# CommonBoard_FK_H743.net
KiCad netlist of a schematic drawn in Altium Designer
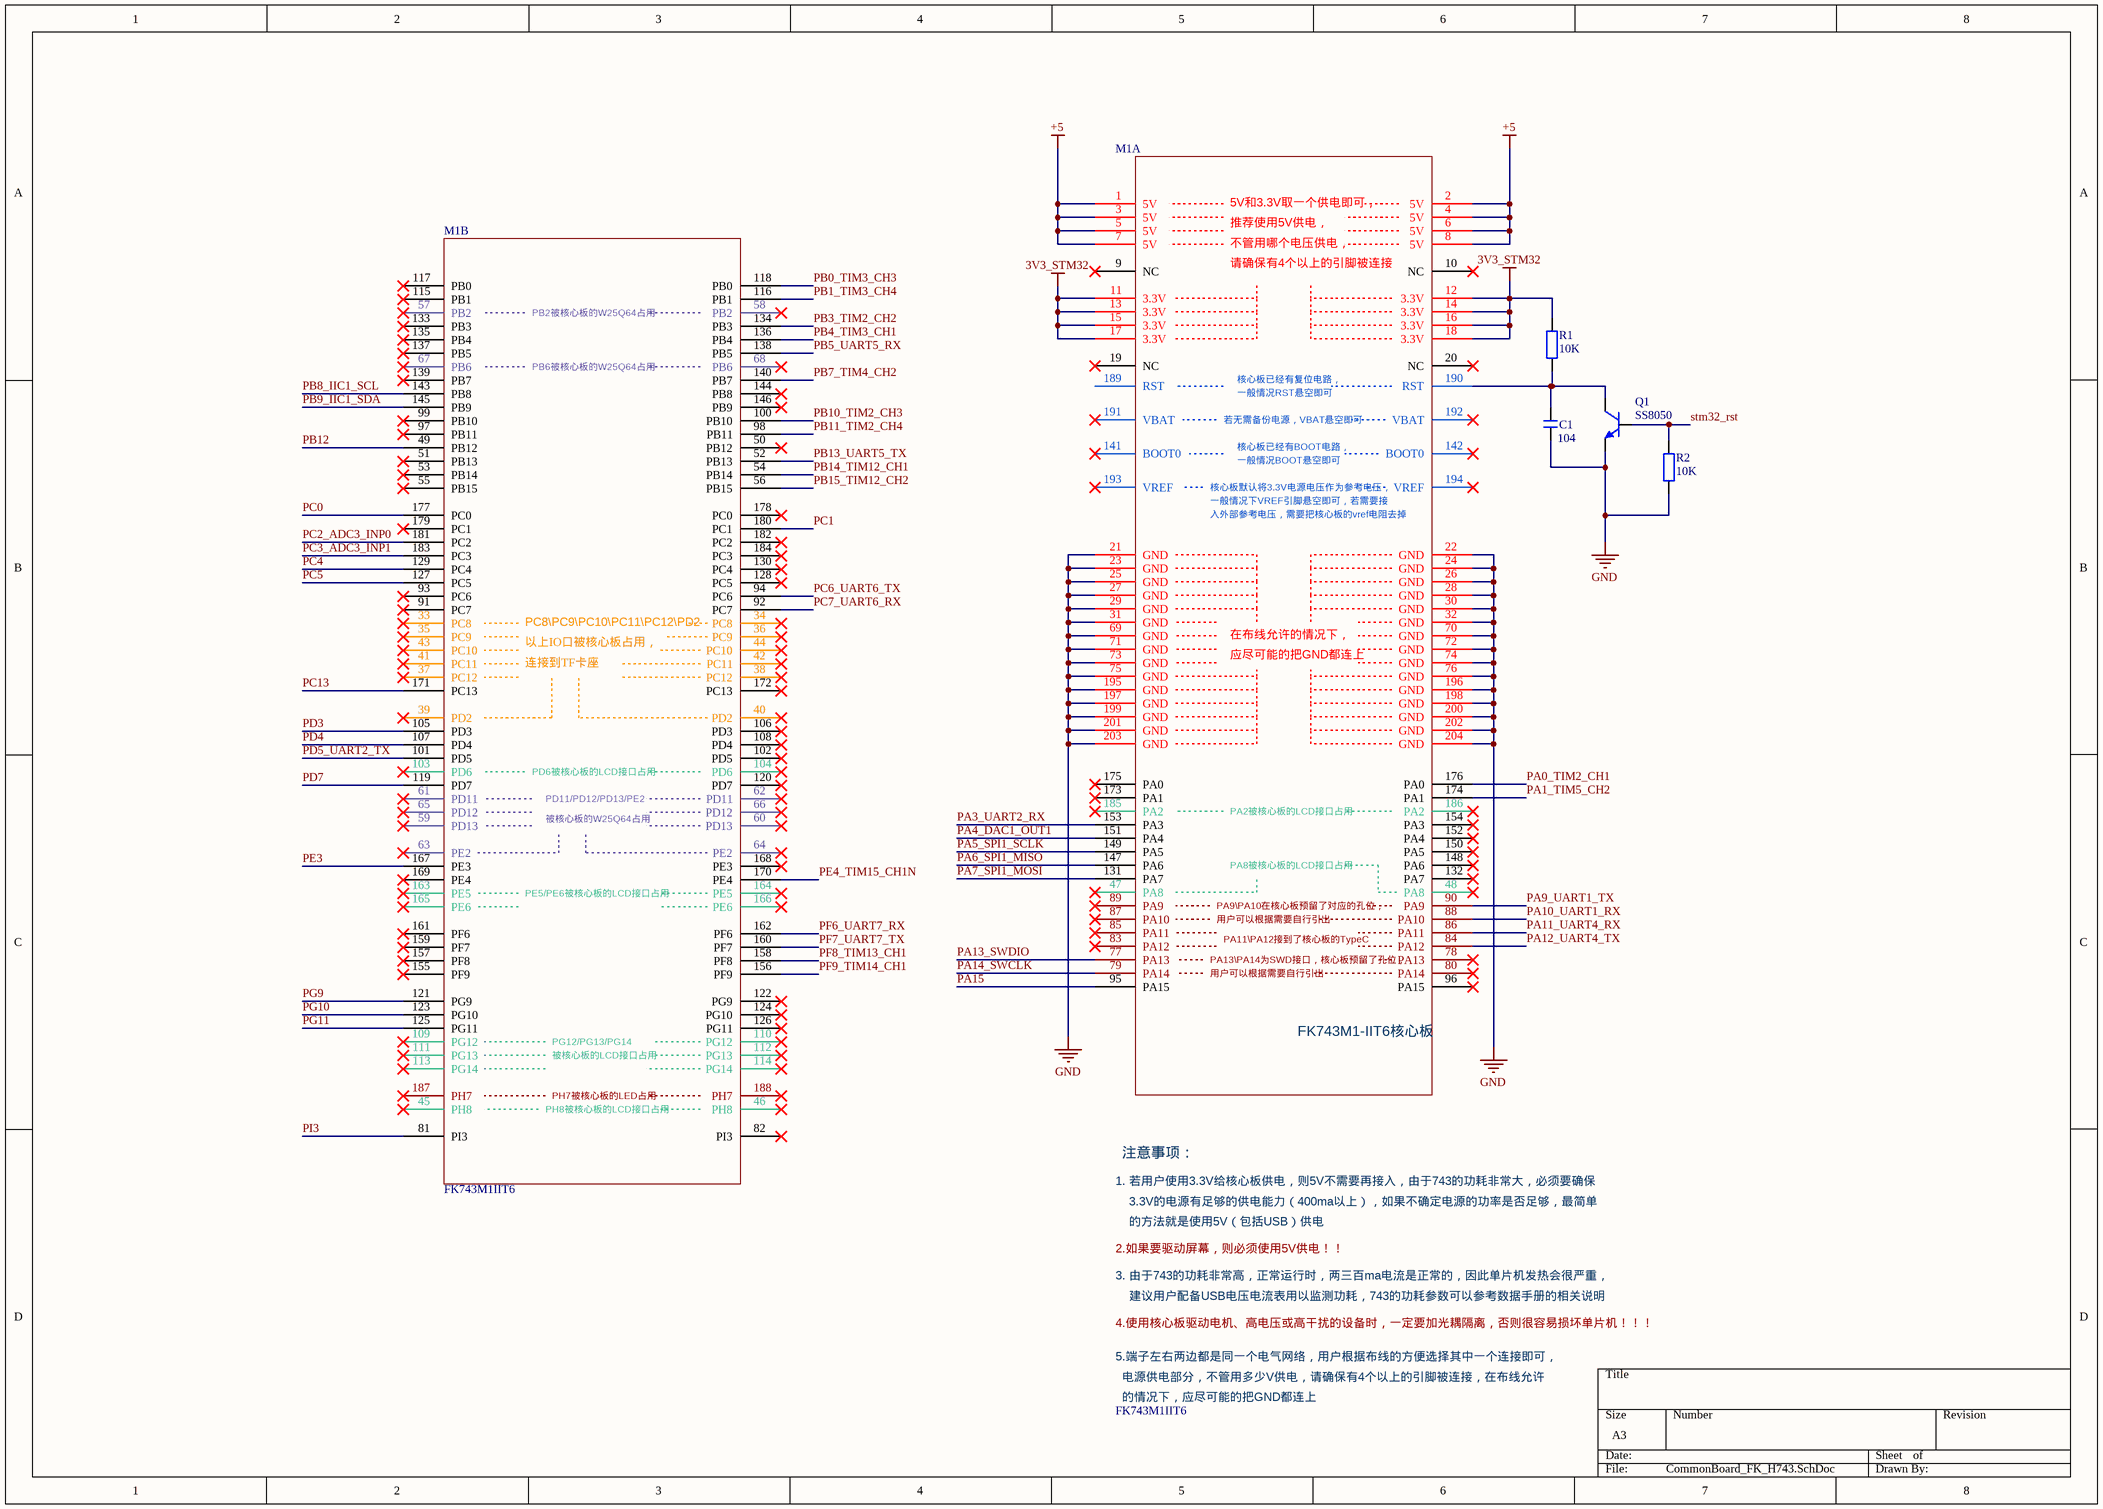
[diagram p0: CommonBoard_FK_H743.SchDoc]

(export (version "E")
  (design (tool "Eeschema 10.0.6"))
  (components
    (comp (ref "C1")
      (value "104")
      (footprint "C 0603_L")
      (description "无极性贴片电容")
      (fields (field (name "版权归属") "源创客"))
      (libsource (lib "3.1   - 电阻-电容-电感") (part "C"))
    )
    (comp (ref "M1")
      (value "FK743M1IIT6")
      (footprint "FK743M1-IIT6")
      (libsource (lib "MySchLib") (part "FK743M1-IIT6"))
    )
    (comp (ref "Q1")
      (value "SS8050")
      (footprint "SOT23-3N")
      (description "高频放大-NPN型")
      (fields (field (name "版权归属") "源创客"))
      (libsource (lib "6.2   - 三极管") (part "8050-SMD"))
    )
    (comp (ref "R1")
      (value "10K")
      (footprint "R 0603_L")
      (description "贴片电阻")
      (fields (field (name "版权归属") "源创客"))
      (libsource (lib "3.1   - 电阻-电容-电感") (part "R"))
    )
    (comp (ref "R2")
      (value "10K")
      (footprint "R 0603_L")
      (description "贴片电阻")
      (fields (field (name "版权归属") "源创客"))
      (libsource (lib "3.1   - 电阻-电容-电感") (part "R"))
    )
  )
  (nets
    (net (code "1") (name "+5") (class "Default")
      (node (ref "M1") (pin "1") (pinfunction "5V_1") (pintype "passive"))
      (node (ref "M1") (pin "2") (pinfunction "5V_2") (pintype "passive"))
      (node (ref "M1") (pin "3") (pinfunction "5V_3") (pintype "passive"))
      (node (ref "M1") (pin "4") (pinfunction "5V_4") (pintype "passive"))
      (node (ref "M1") (pin "5") (pinfunction "5V_5") (pintype "passive"))
      (node (ref "M1") (pin "6") (pinfunction "5V_6") (pintype "passive"))
      (node (ref "M1") (pin "7") (pinfunction "5V_7") (pintype "passive"))
      (node (ref "M1") (pin "8") (pinfunction "5V_8") (pintype "passive"))
    )
    (net (code "2") (name "/PA0_TIM2_CH1") (class "Default")
      (node (ref "M1") (pin "176") (pinfunction "PA0_176") (pintype "passive"))
    )
    (net (code "3") (name "/PA1_TIM5_CH2") (class "Default")
      (node (ref "M1") (pin "174") (pinfunction "PA1_174") (pintype "passive"))
    )
    (net (code "4") (name "/PA3_UART2_RX") (class "Default")
      (node (ref "M1") (pin "153") (pinfunction "PA3_153") (pintype "passive"))
    )
    (net (code "5") (name "/PA4_DAC1_OUT1") (class "Default")
      (node (ref "M1") (pin "151") (pinfunction "PA4_151") (pintype "passive"))
    )
    (net (code "6") (name "/PA5_SPI1_SCLK") (class "Default")
      (node (ref "M1") (pin "149") (pinfunction "PA5_149") (pintype "passive"))
    )
    (net (code "7") (name "/PA6_SPI1_MISO") (class "Default")
      (node (ref "M1") (pin "147") (pinfunction "PA6_147") (pintype "passive"))
    )
    (net (code "8") (name "/PA7_SPI1_MOSI") (class "Default")
      (node (ref "M1") (pin "131") (pinfunction "PA7_131") (pintype "passive"))
    )
    (net (code "9") (name "/PA9_UART1_TX") (class "Default")
      (node (ref "M1") (pin "90") (pinfunction "PA9_90") (pintype "passive"))
    )
    (net (code "10") (name "/PA10_UART1_RX") (class "Default")
      (node (ref "M1") (pin "88") (pinfunction "PA10_88") (pintype "passive"))
    )
    (net (code "11") (name "/PA11_UART4_RX") (class "Default")
      (node (ref "M1") (pin "86") (pinfunction "PA11_86") (pintype "passive"))
    )
    (net (code "12") (name "/PA12_UART4_TX") (class "Default")
      (node (ref "M1") (pin "84") (pinfunction "PA12_84") (pintype "passive"))
    )
    (net (code "13") (name "/PA13_SWDIO") (class "Default")
      (node (ref "M1") (pin "77") (pinfunction "PA13_77") (pintype "passive"))
    )
    (net (code "14") (name "/PA14_SWCLK") (class "Default")
      (node (ref "M1") (pin "79") (pinfunction "PA14_79") (pintype "passive"))
    )
    (net (code "15") (name "/PA15") (class "Default")
      (node (ref "M1") (pin "95") (pinfunction "PA15_95") (pintype "passive"))
    )
    (net (code "16") (name "/PB0_TIM3_CH3") (class "Default")
      (node (ref "M1") (pin "118") (pinfunction "PB0_118") (pintype "passive"))
    )
    (net (code "17") (name "/PB1_TIM3_CH4") (class "Default")
      (node (ref "M1") (pin "116") (pinfunction "PB1_116") (pintype "passive"))
    )
    (net (code "18") (name "/PB3_TIM2_CH2") (class "Default")
      (node (ref "M1") (pin "134") (pinfunction "PB3_134") (pintype "passive"))
    )
    (net (code "19") (name "/PB4_TIM3_CH1") (class "Default")
      (node (ref "M1") (pin "136") (pinfunction "PB4_136") (pintype "passive"))
    )
    (net (code "20") (name "/PB5_UART5_RX") (class "Default")
      (node (ref "M1") (pin "138") (pinfunction "PB5_138") (pintype "passive"))
    )
    (net (code "21") (name "/PB7_TIM4_CH2") (class "Default")
      (node (ref "M1") (pin "140") (pinfunction "PB7_140") (pintype "passive"))
    )
    (net (code "22") (name "/PB8_IIC1_SCL") (class "Default")
      (node (ref "M1") (pin "143") (pinfunction "PB8_143") (pintype "passive"))
    )
    (net (code "23") (name "/PB9_IIC1_SDA") (class "Default")
      (node (ref "M1") (pin "145") (pinfunction "PB9_145") (pintype "passive"))
    )
    (net (code "24") (name "/PB10_TIM2_CH3") (class "Default")
      (node (ref "M1") (pin "100") (pinfunction "PB10_100") (pintype "passive"))
    )
    (net (code "25") (name "/PB11_TIM2_CH4") (class "Default")
      (node (ref "M1") (pin "98") (pinfunction "PB11_98") (pintype "passive"))
    )
    (net (code "26") (name "/PB12") (class "Default")
      (node (ref "M1") (pin "49") (pinfunction "PB12_49") (pintype "passive"))
    )
    (net (code "27") (name "/PB13_UART5_TX") (class "Default")
      (node (ref "M1") (pin "52") (pinfunction "PB13_52") (pintype "passive"))
    )
    (net (code "28") (name "/PB14_TIM12_CH1") (class "Default")
      (node (ref "M1") (pin "54") (pinfunction "PB14_54") (pintype "passive"))
    )
    (net (code "29") (name "/PB15_TIM12_CH2") (class "Default")
      (node (ref "M1") (pin "56") (pinfunction "PB15_56") (pintype "passive"))
    )
    (net (code "30") (name "/PC0") (class "Default")
      (node (ref "M1") (pin "177") (pinfunction "PC0_177") (pintype "passive"))
    )
    (net (code "31") (name "/PC1") (class "Default")
      (node (ref "M1") (pin "180") (pinfunction "PC1_180") (pintype "passive"))
    )
    (net (code "32") (name "/PC2_ADC3_INP0") (class "Default")
      (node (ref "M1") (pin "181") (pinfunction "PC2_181") (pintype "passive"))
    )
    (net (code "33") (name "/PC3_ADC3_INP1") (class "Default")
      (node (ref "M1") (pin "183") (pinfunction "PC3_183") (pintype "passive"))
    )
    (net (code "34") (name "/PC4") (class "Default")
      (node (ref "M1") (pin "129") (pinfunction "PC4_129") (pintype "passive"))
    )
    (net (code "35") (name "/PC5") (class "Default")
      (node (ref "M1") (pin "127") (pinfunction "PC5_127") (pintype "passive"))
    )
    (net (code "36") (name "/PC6_UART6_TX") (class "Default")
      (node (ref "M1") (pin "94") (pinfunction "PC6_94") (pintype "passive"))
    )
    (net (code "37") (name "/PC7_UART6_RX") (class "Default")
      (node (ref "M1") (pin "92") (pinfunction "PC7_92") (pintype "passive"))
    )
    (net (code "38") (name "/PC13") (class "Default")
      (node (ref "M1") (pin "171") (pinfunction "PC13_171") (pintype "passive"))
    )
    (net (code "39") (name "/PD3") (class "Default")
      (node (ref "M1") (pin "105") (pinfunction "PD3_105") (pintype "passive"))
    )
    (net (code "40") (name "/PD4") (class "Default")
      (node (ref "M1") (pin "107") (pinfunction "PD4_107") (pintype "passive"))
    )
    (net (code "41") (name "/PD5_UART2_TX") (class "Default")
      (node (ref "M1") (pin "101") (pinfunction "PD5_101") (pintype "passive"))
    )
    (net (code "42") (name "/PD7") (class "Default")
      (node (ref "M1") (pin "119") (pinfunction "PD7_119") (pintype "passive"))
    )
    (net (code "43") (name "/PE3") (class "Default")
      (node (ref "M1") (pin "167") (pinfunction "PE3_167") (pintype "passive"))
    )
    (net (code "44") (name "/PE4_TIM15_CH1N") (class "Default")
      (node (ref "M1") (pin "170") (pinfunction "PE4_170") (pintype "passive"))
    )
    (net (code "45") (name "/PF6_UART7_RX") (class "Default")
      (node (ref "M1") (pin "162") (pinfunction "PF6_162") (pintype "passive"))
    )
    (net (code "46") (name "/PF7_UART7_TX") (class "Default")
      (node (ref "M1") (pin "160") (pinfunction "PF7_160") (pintype "passive"))
    )
    (net (code "47") (name "/PF8_TIM13_CH1") (class "Default")
      (node (ref "M1") (pin "158") (pinfunction "PF8_158") (pintype "passive"))
    )
    (net (code "48") (name "/PF9_TIM14_CH1") (class "Default")
      (node (ref "M1") (pin "156") (pinfunction "PF9_156") (pintype "passive"))
    )
    (net (code "49") (name "/PG9") (class "Default")
      (node (ref "M1") (pin "121") (pinfunction "PG9_121") (pintype "passive"))
    )
    (net (code "50") (name "/PG10") (class "Default")
      (node (ref "M1") (pin "123") (pinfunction "PG10_123") (pintype "passive"))
    )
    (net (code "51") (name "/PG11") (class "Default")
      (node (ref "M1") (pin "125") (pinfunction "PG11_125") (pintype "passive"))
    )
    (net (code "52") (name "/PI3") (class "Default")
      (node (ref "M1") (pin "81") (pinfunction "PI3_81") (pintype "passive"))
    )
    (net (code "53") (name "/stm32_rst") (class "Default")
      (node (ref "Q1") (pin "1") (pinfunction "B_1") (pintype "passive"))
      (node (ref "R2") (pin "2") (pinfunction "2_2") (pintype "passive"))
    )
    (net (code "54") (name "3V3_STM32") (class "Default")
      (node (ref "M1") (pin "11") (pinfunction "3.3V_11") (pintype "passive"))
      (node (ref "M1") (pin "12") (pinfunction "3.3V_12") (pintype "passive"))
      (node (ref "M1") (pin "13") (pinfunction "3.3V_13") (pintype "passive"))
      (node (ref "M1") (pin "14") (pinfunction "3.3V_14") (pintype "passive"))
      (node (ref "M1") (pin "15") (pinfunction "3.3V_15") (pintype "passive"))
      (node (ref "M1") (pin "16") (pinfunction "3.3V_16") (pintype "passive"))
      (node (ref "M1") (pin "17") (pinfunction "3.3V_17") (pintype "passive"))
      (node (ref "M1") (pin "18") (pinfunction "3.3V_18") (pintype "passive"))
      (node (ref "R1") (pin "2") (pinfunction "2_2") (pintype "passive"))
    )
    (net (code "55") (name "GND") (class "Default")
      (node (ref "C1") (pin "1") (pinfunction "1_1") (pintype "passive"))
      (node (ref "M1") (pin "195") (pinfunction "GND_195") (pintype "passive"))
      (node (ref "M1") (pin "196") (pinfunction "GND_196") (pintype "passive"))
      (node (ref "M1") (pin "197") (pinfunction "GND_197") (pintype "passive"))
      (node (ref "M1") (pin "198") (pinfunction "GND_198") (pintype "passive"))
      (node (ref "M1") (pin "199") (pinfunction "GND_199") (pintype "passive"))
      (node (ref "M1") (pin "200") (pinfunction "GND_200") (pintype "passive"))
      (node (ref "M1") (pin "201") (pinfunction "GND_201") (pintype "passive"))
      (node (ref "M1") (pin "202") (pinfunction "GND_202") (pintype "passive"))
      (node (ref "M1") (pin "203") (pinfunction "GND_203") (pintype "passive"))
      (node (ref "M1") (pin "204") (pinfunction "GND_204") (pintype "passive"))
      (node (ref "M1") (pin "21") (pinfunction "GND_21") (pintype "passive"))
      (node (ref "M1") (pin "22") (pinfunction "GND_22") (pintype "passive"))
      (node (ref "M1") (pin "23") (pinfunction "GND_23") (pintype "passive"))
      (node (ref "M1") (pin "24") (pinfunction "GND_24") (pintype "passive"))
      (node (ref "M1") (pin "25") (pinfunction "GND_25") (pintype "passive"))
      (node (ref "M1") (pin "26") (pinfunction "GND_26") (pintype "passive"))
      (node (ref "M1") (pin "27") (pinfunction "GND_27") (pintype "passive"))
      (node (ref "M1") (pin "28") (pinfunction "GND_28") (pintype "passive"))
      (node (ref "M1") (pin "29") (pinfunction "GND_29") (pintype "passive"))
      (node (ref "M1") (pin "30") (pinfunction "GND_30") (pintype "passive"))
      (node (ref "M1") (pin "31") (pinfunction "GND_31") (pintype "passive"))
      (node (ref "M1") (pin "32") (pinfunction "GND_32") (pintype "passive"))
      (node (ref "M1") (pin "69") (pinfunction "GND_69") (pintype "passive"))
      (node (ref "M1") (pin "70") (pinfunction "GND_70") (pintype "passive"))
      (node (ref "M1") (pin "71") (pinfunction "GND_71") (pintype "passive"))
      (node (ref "M1") (pin "72") (pinfunction "GND_72") (pintype "passive"))
      (node (ref "M1") (pin "73") (pinfunction "GND_73") (pintype "passive"))
      (node (ref "M1") (pin "74") (pinfunction "GND_74") (pintype "passive"))
      (node (ref "M1") (pin "75") (pinfunction "GND_75") (pintype "passive"))
      (node (ref "M1") (pin "76") (pinfunction "GND_76") (pintype "passive"))
      (node (ref "Q1") (pin "2") (pinfunction "E_2") (pintype "passive"))
      (node (ref "R2") (pin "1") (pinfunction "1_1") (pintype "passive"))
    )
    (net (code "56") (name "Net-(Q1-C)") (class "Default")
      (node (ref "C1") (pin "2") (pinfunction "2_2") (pintype "passive"))
      (node (ref "M1") (pin "190") (pinfunction "RST_190") (pintype "passive"))
      (node (ref "Q1") (pin "3") (pinfunction "C_3") (pintype "passive"))
      (node (ref "R1") (pin "1") (pinfunction "1_1") (pintype "passive"))
    )
    (net (code "57") (name "unconnected-(M1A-BOOT0-Pad141)") (class "Default")
      (node (ref "M1") (pin "141") (pinfunction "BOOT0_141") (pintype "passive+no_connect"))
    )
    (net (code "58") (name "unconnected-(M1A-BOOT0-Pad142)") (class "Default")
      (node (ref "M1") (pin "142") (pinfunction "BOOT0_142") (pintype "passive+no_connect"))
    )
    (net (code "59") (name "unconnected-(M1A-NC-Pad9)") (class "Default")
      (node (ref "M1") (pin "9") (pinfunction "NC_9") (pintype "passive+no_connect"))
    )
    (net (code "60") (name "unconnected-(M1A-NC-Pad10)") (class "Default")
      (node (ref "M1") (pin "10") (pinfunction "NC_10") (pintype "passive+no_connect"))
    )
    (net (code "61") (name "unconnected-(M1A-NC-Pad19)") (class "Default")
      (node (ref "M1") (pin "19") (pinfunction "NC_19") (pintype "passive+no_connect"))
    )
    (net (code "62") (name "unconnected-(M1A-NC-Pad20)") (class "Default")
      (node (ref "M1") (pin "20") (pinfunction "NC_20") (pintype "passive+no_connect"))
    )
    (net (code "63") (name "unconnected-(M1A-PA0-Pad175)") (class "Default")
      (node (ref "M1") (pin "175") (pinfunction "PA0_175") (pintype "passive+no_connect"))
    )
    (net (code "64") (name "unconnected-(M1A-PA1-Pad173)") (class "Default")
      (node (ref "M1") (pin "173") (pinfunction "PA1_173") (pintype "passive+no_connect"))
    )
    (net (code "65") (name "unconnected-(M1A-PA2-Pad185)") (class "Default")
      (node (ref "M1") (pin "185") (pinfunction "PA2_185") (pintype "passive+no_connect"))
    )
    (net (code "66") (name "unconnected-(M1A-PA2-Pad186)") (class "Default")
      (node (ref "M1") (pin "186") (pinfunction "PA2_186") (pintype "passive+no_connect"))
    )
    (net (code "67") (name "unconnected-(M1A-PA3-Pad154)") (class "Default")
      (node (ref "M1") (pin "154") (pinfunction "PA3_154") (pintype "passive+no_connect"))
    )
    (net (code "68") (name "unconnected-(M1A-PA4-Pad152)") (class "Default")
      (node (ref "M1") (pin "152") (pinfunction "PA4_152") (pintype "passive+no_connect"))
    )
    (net (code "69") (name "unconnected-(M1A-PA5-Pad150)") (class "Default")
      (node (ref "M1") (pin "150") (pinfunction "PA5_150") (pintype "passive+no_connect"))
    )
    (net (code "70") (name "unconnected-(M1A-PA6-Pad148)") (class "Default")
      (node (ref "M1") (pin "148") (pinfunction "PA6_148") (pintype "passive+no_connect"))
    )
    (net (code "71") (name "unconnected-(M1A-PA7-Pad132)") (class "Default")
      (node (ref "M1") (pin "132") (pinfunction "PA7_132") (pintype "passive+no_connect"))
    )
    (net (code "72") (name "unconnected-(M1A-PA8-Pad47)") (class "Default")
      (node (ref "M1") (pin "47") (pinfunction "PA8_47") (pintype "passive+no_connect"))
    )
    (net (code "73") (name "unconnected-(M1A-PA8-Pad48)") (class "Default")
      (node (ref "M1") (pin "48") (pinfunction "PA8_48") (pintype "passive+no_connect"))
    )
    (net (code "74") (name "unconnected-(M1A-PA9-Pad89)") (class "Default")
      (node (ref "M1") (pin "89") (pinfunction "PA9_89") (pintype "passive+no_connect"))
    )
    (net (code "75") (name "unconnected-(M1A-PA10-Pad87)") (class "Default")
      (node (ref "M1") (pin "87") (pinfunction "PA10_87") (pintype "passive+no_connect"))
    )
    (net (code "76") (name "unconnected-(M1A-PA11-Pad85)") (class "Default")
      (node (ref "M1") (pin "85") (pinfunction "PA11_85") (pintype "passive+no_connect"))
    )
    (net (code "77") (name "unconnected-(M1A-PA12-Pad83)") (class "Default")
      (node (ref "M1") (pin "83") (pinfunction "PA12_83") (pintype "passive+no_connect"))
    )
    (net (code "78") (name "unconnected-(M1A-PA13-Pad78)") (class "Default")
      (node (ref "M1") (pin "78") (pinfunction "PA13_78") (pintype "passive+no_connect"))
    )
    (net (code "79") (name "unconnected-(M1A-PA14-Pad80)") (class "Default")
      (node (ref "M1") (pin "80") (pinfunction "PA14_80") (pintype "passive+no_connect"))
    )
    (net (code "80") (name "unconnected-(M1A-PA15-Pad96)") (class "Default")
      (node (ref "M1") (pin "96") (pinfunction "PA15_96") (pintype "passive+no_connect"))
    )
    (net (code "81") (name "unconnected-(M1A-RST-Pad189)") (class "Default")
      (node (ref "M1") (pin "189") (pinfunction "RST_189") (pintype "passive"))
    )
    (net (code "82") (name "unconnected-(M1A-VBAT-Pad191)") (class "Default")
      (node (ref "M1") (pin "191") (pinfunction "VBAT_191") (pintype "passive+no_connect"))
    )
    (net (code "83") (name "unconnected-(M1A-VBAT-Pad192)") (class "Default")
      (node (ref "M1") (pin "192") (pinfunction "VBAT_192") (pintype "passive+no_connect"))
    )
    (net (code "84") (name "unconnected-(M1A-VREF-Pad193)") (class "Default")
      (node (ref "M1") (pin "193") (pinfunction "VREF_193") (pintype "passive+no_connect"))
    )
    (net (code "85") (name "unconnected-(M1A-VREF-Pad194)") (class "Default")
      (node (ref "M1") (pin "194") (pinfunction "VREF_194") (pintype "passive+no_connect"))
    )
    (net (code "86") (name "unconnected-(M1B-PB0-Pad117)") (class "Default")
      (node (ref "M1") (pin "117") (pinfunction "PB0_117") (pintype "passive+no_connect"))
    )
    (net (code "87") (name "unconnected-(M1B-PB1-Pad115)") (class "Default")
      (node (ref "M1") (pin "115") (pinfunction "PB1_115") (pintype "passive+no_connect"))
    )
    (net (code "88") (name "unconnected-(M1B-PB2-Pad57)") (class "Default")
      (node (ref "M1") (pin "57") (pinfunction "PB2_57") (pintype "passive+no_connect"))
    )
    (net (code "89") (name "unconnected-(M1B-PB2-Pad58)") (class "Default")
      (node (ref "M1") (pin "58") (pinfunction "PB2_58") (pintype "passive+no_connect"))
    )
    (net (code "90") (name "unconnected-(M1B-PB3-Pad133)") (class "Default")
      (node (ref "M1") (pin "133") (pinfunction "PB3_133") (pintype "passive+no_connect"))
    )
    (net (code "91") (name "unconnected-(M1B-PB4-Pad135)") (class "Default")
      (node (ref "M1") (pin "135") (pinfunction "PB4_135") (pintype "passive+no_connect"))
    )
    (net (code "92") (name "unconnected-(M1B-PB5-Pad137)") (class "Default")
      (node (ref "M1") (pin "137") (pinfunction "PB5_137") (pintype "passive+no_connect"))
    )
    (net (code "93") (name "unconnected-(M1B-PB6-Pad67)") (class "Default")
      (node (ref "M1") (pin "67") (pinfunction "PB6_67") (pintype "passive+no_connect"))
    )
    (net (code "94") (name "unconnected-(M1B-PB6-Pad68)") (class "Default")
      (node (ref "M1") (pin "68") (pinfunction "PB6_68") (pintype "passive+no_connect"))
    )
    (net (code "95") (name "unconnected-(M1B-PB7-Pad139)") (class "Default")
      (node (ref "M1") (pin "139") (pinfunction "PB7_139") (pintype "passive+no_connect"))
    )
    (net (code "96") (name "unconnected-(M1B-PB8-Pad144)") (class "Default")
      (node (ref "M1") (pin "144") (pinfunction "PB8_144") (pintype "passive+no_connect"))
    )
    (net (code "97") (name "unconnected-(M1B-PB9-Pad146)") (class "Default")
      (node (ref "M1") (pin "146") (pinfunction "PB9_146") (pintype "passive+no_connect"))
    )
    (net (code "98") (name "unconnected-(M1B-PB10-Pad99)") (class "Default")
      (node (ref "M1") (pin "99") (pinfunction "PB10_99") (pintype "passive+no_connect"))
    )
    (net (code "99") (name "unconnected-(M1B-PB11-Pad97)") (class "Default")
      (node (ref "M1") (pin "97") (pinfunction "PB11_97") (pintype "passive+no_connect"))
    )
    (net (code "100") (name "unconnected-(M1B-PB12-Pad50)") (class "Default")
      (node (ref "M1") (pin "50") (pinfunction "PB12_50") (pintype "passive+no_connect"))
    )
    (net (code "101") (name "unconnected-(M1B-PB13-Pad51)") (class "Default")
      (node (ref "M1") (pin "51") (pinfunction "PB13_51") (pintype "passive+no_connect"))
    )
    (net (code "102") (name "unconnected-(M1B-PB14-Pad53)") (class "Default")
      (node (ref "M1") (pin "53") (pinfunction "PB14_53") (pintype "passive+no_connect"))
    )
    (net (code "103") (name "unconnected-(M1B-PB15-Pad55)") (class "Default")
      (node (ref "M1") (pin "55") (pinfunction "PB15_55") (pintype "passive+no_connect"))
    )
    (net (code "104") (name "unconnected-(M1B-PC0-Pad178)") (class "Default")
      (node (ref "M1") (pin "178") (pinfunction "PC0_178") (pintype "passive+no_connect"))
    )
    (net (code "105") (name "unconnected-(M1B-PC1-Pad179)") (class "Default")
      (node (ref "M1") (pin "179") (pinfunction "PC1_179") (pintype "passive+no_connect"))
    )
    (net (code "106") (name "unconnected-(M1B-PC2-Pad182)") (class "Default")
      (node (ref "M1") (pin "182") (pinfunction "PC2_182") (pintype "passive+no_connect"))
    )
    (net (code "107") (name "unconnected-(M1B-PC3-Pad184)") (class "Default")
      (node (ref "M1") (pin "184") (pinfunction "PC3_184") (pintype "passive+no_connect"))
    )
    (net (code "108") (name "unconnected-(M1B-PC4-Pad130)") (class "Default")
      (node (ref "M1") (pin "130") (pinfunction "PC4_130") (pintype "passive+no_connect"))
    )
    (net (code "109") (name "unconnected-(M1B-PC5-Pad128)") (class "Default")
      (node (ref "M1") (pin "128") (pinfunction "PC5_128") (pintype "passive+no_connect"))
    )
    (net (code "110") (name "unconnected-(M1B-PC6-Pad93)") (class "Default")
      (node (ref "M1") (pin "93") (pinfunction "PC6_93") (pintype "passive+no_connect"))
    )
    (net (code "111") (name "unconnected-(M1B-PC7-Pad91)") (class "Default")
      (node (ref "M1") (pin "91") (pinfunction "PC7_91") (pintype "passive+no_connect"))
    )
    (net (code "112") (name "unconnected-(M1B-PC8-Pad33)") (class "Default")
      (node (ref "M1") (pin "33") (pinfunction "PC8_33") (pintype "passive+no_connect"))
    )
    (net (code "113") (name "unconnected-(M1B-PC8-Pad34)") (class "Default")
      (node (ref "M1") (pin "34") (pinfunction "PC8_34") (pintype "passive+no_connect"))
    )
    (net (code "114") (name "unconnected-(M1B-PC9-Pad35)") (class "Default")
      (node (ref "M1") (pin "35") (pinfunction "PC9_35") (pintype "passive+no_connect"))
    )
    (net (code "115") (name "unconnected-(M1B-PC9-Pad36)") (class "Default")
      (node (ref "M1") (pin "36") (pinfunction "PC9_36") (pintype "passive+no_connect"))
    )
    (net (code "116") (name "unconnected-(M1B-PC10-Pad43)") (class "Default")
      (node (ref "M1") (pin "43") (pinfunction "PC10_43") (pintype "passive+no_connect"))
    )
    (net (code "117") (name "unconnected-(M1B-PC10-Pad44)") (class "Default")
      (node (ref "M1") (pin "44") (pinfunction "PC10_44") (pintype "passive+no_connect"))
    )
    (net (code "118") (name "unconnected-(M1B-PC11-Pad41)") (class "Default")
      (node (ref "M1") (pin "41") (pinfunction "PC11_41") (pintype "passive+no_connect"))
    )
    (net (code "119") (name "unconnected-(M1B-PC11-Pad42)") (class "Default")
      (node (ref "M1") (pin "42") (pinfunction "PC11_42") (pintype "passive+no_connect"))
    )
    (net (code "120") (name "unconnected-(M1B-PC12-Pad37)") (class "Default")
      (node (ref "M1") (pin "37") (pinfunction "PC12_37") (pintype "passive+no_connect"))
    )
    (net (code "121") (name "unconnected-(M1B-PC12-Pad38)") (class "Default")
      (node (ref "M1") (pin "38") (pinfunction "PC12_38") (pintype "passive+no_connect"))
    )
    (net (code "122") (name "unconnected-(M1B-PC13-Pad172)") (class "Default")
      (node (ref "M1") (pin "172") (pinfunction "PC13_172") (pintype "passive+no_connect"))
    )
    (net (code "123") (name "unconnected-(M1B-PD2-Pad39)") (class "Default")
      (node (ref "M1") (pin "39") (pinfunction "PD2_39") (pintype "passive+no_connect"))
    )
    (net (code "124") (name "unconnected-(M1B-PD2-Pad40)") (class "Default")
      (node (ref "M1") (pin "40") (pinfunction "PD2_40") (pintype "passive+no_connect"))
    )
    (net (code "125") (name "unconnected-(M1B-PD3-Pad106)") (class "Default")
      (node (ref "M1") (pin "106") (pinfunction "PD3_106") (pintype "passive+no_connect"))
    )
    (net (code "126") (name "unconnected-(M1B-PD4-Pad108)") (class "Default")
      (node (ref "M1") (pin "108") (pinfunction "PD4_108") (pintype "passive+no_connect"))
    )
    (net (code "127") (name "unconnected-(M1B-PD5-Pad102)") (class "Default")
      (node (ref "M1") (pin "102") (pinfunction "PD5_102") (pintype "passive+no_connect"))
    )
    (net (code "128") (name "unconnected-(M1B-PD6-Pad103)") (class "Default")
      (node (ref "M1") (pin "103") (pinfunction "PD6_103") (pintype "passive+no_connect"))
    )
    (net (code "129") (name "unconnected-(M1B-PD6-Pad104)") (class "Default")
      (node (ref "M1") (pin "104") (pinfunction "PD6_104") (pintype "passive+no_connect"))
    )
    (net (code "130") (name "unconnected-(M1B-PD7-Pad120)") (class "Default")
      (node (ref "M1") (pin "120") (pinfunction "PD7_120") (pintype "passive+no_connect"))
    )
    (net (code "131") (name "unconnected-(M1B-PD11-Pad61)") (class "Default")
      (node (ref "M1") (pin "61") (pinfunction "PD11_61") (pintype "passive+no_connect"))
    )
    (net (code "132") (name "unconnected-(M1B-PD11-Pad62)") (class "Default")
      (node (ref "M1") (pin "62") (pinfunction "PD11_62") (pintype "passive+no_connect"))
    )
    (net (code "133") (name "unconnected-(M1B-PD12-Pad65)") (class "Default")
      (node (ref "M1") (pin "65") (pinfunction "PD12_65") (pintype "passive+no_connect"))
    )
    (net (code "134") (name "unconnected-(M1B-PD12-Pad66)") (class "Default")
      (node (ref "M1") (pin "66") (pinfunction "PD12_66") (pintype "passive+no_connect"))
    )
    (net (code "135") (name "unconnected-(M1B-PD13-Pad59)") (class "Default")
      (node (ref "M1") (pin "59") (pinfunction "PD13_59") (pintype "passive+no_connect"))
    )
    (net (code "136") (name "unconnected-(M1B-PD13-Pad60)") (class "Default")
      (node (ref "M1") (pin "60") (pinfunction "PD13_60") (pintype "passive+no_connect"))
    )
    (net (code "137") (name "unconnected-(M1B-PE2-Pad63)") (class "Default")
      (node (ref "M1") (pin "63") (pinfunction "PE2_63") (pintype "passive+no_connect"))
    )
    (net (code "138") (name "unconnected-(M1B-PE2-Pad64)") (class "Default")
      (node (ref "M1") (pin "64") (pinfunction "PE2_64") (pintype "passive+no_connect"))
    )
    (net (code "139") (name "unconnected-(M1B-PE3-Pad168)") (class "Default")
      (node (ref "M1") (pin "168") (pinfunction "PE3_168") (pintype "passive+no_connect"))
    )
    (net (code "140") (name "unconnected-(M1B-PE4-Pad169)") (class "Default")
      (node (ref "M1") (pin "169") (pinfunction "PE4_169") (pintype "passive+no_connect"))
    )
    (net (code "141") (name "unconnected-(M1B-PE5-Pad163)") (class "Default")
      (node (ref "M1") (pin "163") (pinfunction "PE5_163") (pintype "passive+no_connect"))
    )
    (net (code "142") (name "unconnected-(M1B-PE5-Pad164)") (class "Default")
      (node (ref "M1") (pin "164") (pinfunction "PE5_164") (pintype "passive+no_connect"))
    )
    (net (code "143") (name "unconnected-(M1B-PE6-Pad165)") (class "Default")
      (node (ref "M1") (pin "165") (pinfunction "PE6_165") (pintype "passive+no_connect"))
    )
    (net (code "144") (name "unconnected-(M1B-PE6-Pad166)") (class "Default")
      (node (ref "M1") (pin "166") (pinfunction "PE6_166") (pintype "passive+no_connect"))
    )
    (net (code "145") (name "unconnected-(M1B-PF6-Pad161)") (class "Default")
      (node (ref "M1") (pin "161") (pinfunction "PF6_161") (pintype "passive+no_connect"))
    )
    (net (code "146") (name "unconnected-(M1B-PF7-Pad159)") (class "Default")
      (node (ref "M1") (pin "159") (pinfunction "PF7_159") (pintype "passive+no_connect"))
    )
    (net (code "147") (name "unconnected-(M1B-PF8-Pad157)") (class "Default")
      (node (ref "M1") (pin "157") (pinfunction "PF8_157") (pintype "passive+no_connect"))
    )
    (net (code "148") (name "unconnected-(M1B-PF9-Pad155)") (class "Default")
      (node (ref "M1") (pin "155") (pinfunction "PF9_155") (pintype "passive+no_connect"))
    )
    (net (code "149") (name "unconnected-(M1B-PG9-Pad122)") (class "Default")
      (node (ref "M1") (pin "122") (pinfunction "PG9_122") (pintype "passive+no_connect"))
    )
    (net (code "150") (name "unconnected-(M1B-PG10-Pad124)") (class "Default")
      (node (ref "M1") (pin "124") (pinfunction "PG10_124") (pintype "passive+no_connect"))
    )
    (net (code "151") (name "unconnected-(M1B-PG11-Pad126)") (class "Default")
      (node (ref "M1") (pin "126") (pinfunction "PG11_126") (pintype "passive+no_connect"))
    )
    (net (code "152") (name "unconnected-(M1B-PG12-Pad109)") (class "Default")
      (node (ref "M1") (pin "109") (pinfunction "PG12_109") (pintype "passive+no_connect"))
    )
    (net (code "153") (name "unconnected-(M1B-PG12-Pad110)") (class "Default")
      (node (ref "M1") (pin "110") (pinfunction "PG12_110") (pintype "passive+no_connect"))
    )
    (net (code "154") (name "unconnected-(M1B-PG13-Pad111)") (class "Default")
      (node (ref "M1") (pin "111") (pinfunction "PG13_111") (pintype "passive+no_connect"))
    )
    (net (code "155") (name "unconnected-(M1B-PG13-Pad112)") (class "Default")
      (node (ref "M1") (pin "112") (pinfunction "PG13_112") (pintype "passive+no_connect"))
    )
    (net (code "156") (name "unconnected-(M1B-PG14-Pad113)") (class "Default")
      (node (ref "M1") (pin "113") (pinfunction "PG14_113") (pintype "passive+no_connect"))
    )
    (net (code "157") (name "unconnected-(M1B-PG14-Pad114)") (class "Default")
      (node (ref "M1") (pin "114") (pinfunction "PG14_114") (pintype "passive+no_connect"))
    )
    (net (code "158") (name "unconnected-(M1B-PH7-Pad187)") (class "Default")
      (node (ref "M1") (pin "187") (pinfunction "PH7_187") (pintype "passive+no_connect"))
    )
    (net (code "159") (name "unconnected-(M1B-PH7-Pad188)") (class "Default")
      (node (ref "M1") (pin "188") (pinfunction "PH7_188") (pintype "passive+no_connect"))
    )
    (net (code "160") (name "unconnected-(M1B-PH8-Pad45)") (class "Default")
      (node (ref "M1") (pin "45") (pinfunction "PH8_45") (pintype "passive+no_connect"))
    )
    (net (code "161") (name "unconnected-(M1B-PH8-Pad46)") (class "Default")
      (node (ref "M1") (pin "46") (pinfunction "PH8_46") (pintype "passive+no_connect"))
    )
    (net (code "162") (name "unconnected-(M1B-PI3-Pad82)") (class "Default")
      (node (ref "M1") (pin "82") (pinfunction "PI3_82") (pintype "passive+no_connect"))
    )
  )
)
